# Antenna_Board_v4_1.net
KiCad netlist of a schematic drawn in EAGLE
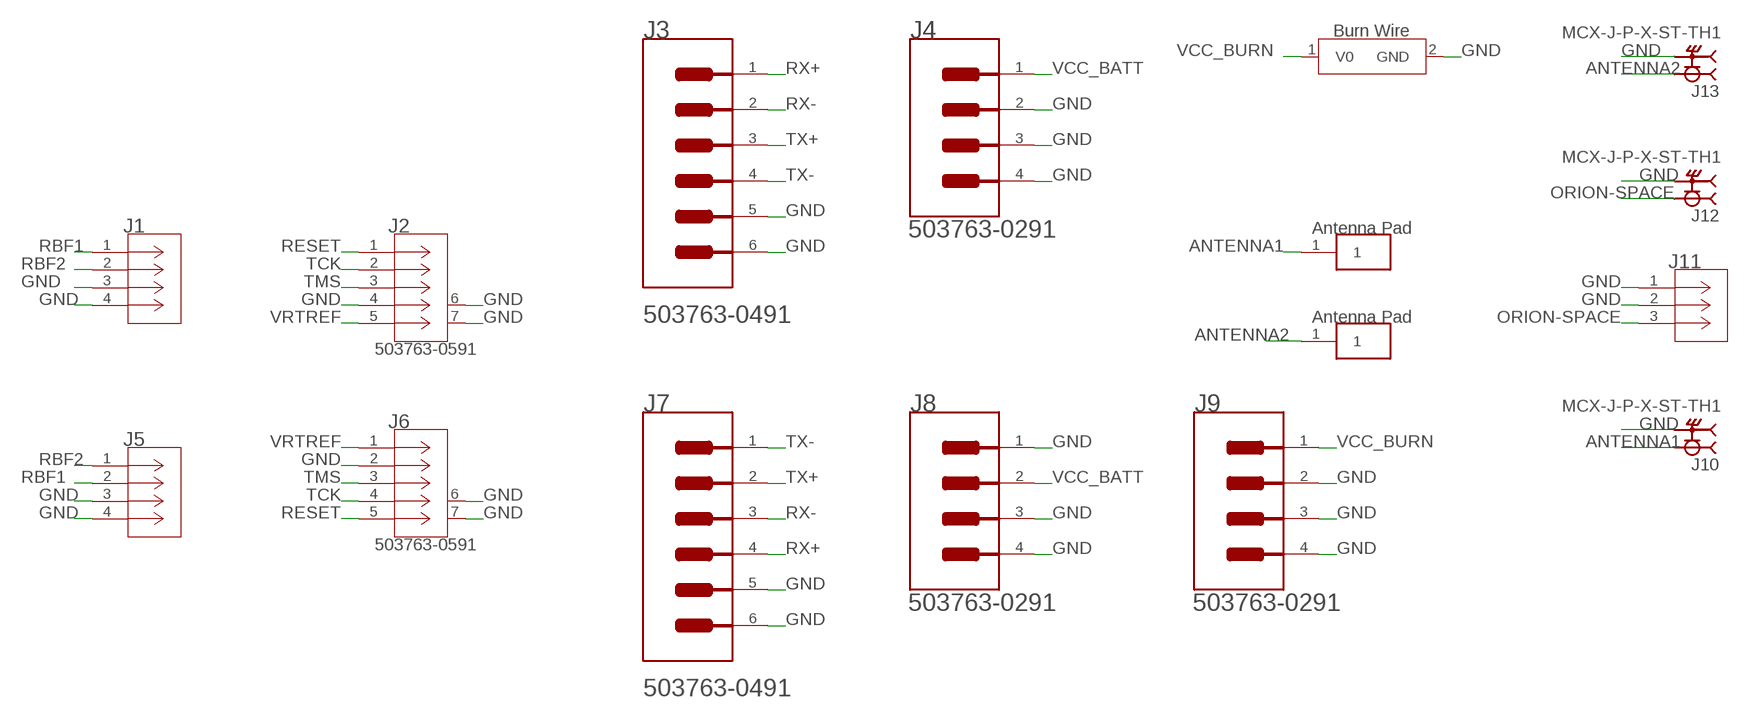
[diagram p0: schematic, sheet 1]

(export (version "E")
  (design (tool "Eeschema 10.0.6"))
  (components
    (comp (ref "J1")
      (value "5037630291")
      (footprint "eagle-import:CON_5037630291")
      (fields (field (name "COPYRIGHT") "Copyright (C) 2018 Accelerated Designs. All rights reserved"))
      (libsource (lib "eagle-import") (part "5037630291"))
    )
    (comp (ref "J2")
      (value "503763-0591")
      (footprint "eagle-import:CONN_5037630591_MOL")
      (fields (field (name "COPYRIGHT") "Copyright (C) 2018 Accelerated Designs. All rights reserved"))
      (libsource (lib "eagle-import") (part "503763-0591"))
    )
    (comp (ref "J3")
      (value "MOLEX_503763-0491MOLEX_503763-0491_0_0")
      (footprint "eagle-import:MOLEX_503763-0491_0")
      (fields
        (field (name "DIGIKEY_PART_NUMBER") "WM10655CT-ND")
        (field (name "MF") "Molex")
        (field (name "MOUSER_PART_NUMBER") "538-503763-0491")
      )
      (libsource (lib "eagle-import") (part "MOLEX_503763-0491MOLEX_503763-0491_0_0"))
    )
    (comp (ref "J4")
      (value "MOLEX_503763-0291MOLEX_503763-0291_0_0")
      (footprint "eagle-import:MOLEX_503763-0291_0")
      (fields
        (field (name "DIGIKEY_PART_NUMBER") "WM10654CT-ND")
        (field (name "MF") "Molex")
        (field (name "MOUSER_PART_NUMBER") "538-503763-0291")
      )
      (libsource (lib "eagle-import") (part "MOLEX_503763-0291MOLEX_503763-0291_0_0"))
    )
    (comp (ref "J5")
      (value "5037630291")
      (footprint "eagle-import:CON_5037630291")
      (fields (field (name "COPYRIGHT") "Copyright (C) 2018 Accelerated Designs. All rights reserved"))
      (libsource (lib "eagle-import") (part "5037630291"))
    )
    (comp (ref "J6")
      (value "503763-0591")
      (footprint "eagle-import:CONN_5037630591_MOL")
      (fields (field (name "COPYRIGHT") "Copyright (C) 2018 Accelerated Designs. All rights reserved"))
      (libsource (lib "eagle-import") (part "503763-0591"))
    )
    (comp (ref "J7")
      (value "MOLEX_503763-0491MOLEX_503763-0491_0_0")
      (footprint "eagle-import:MOLEX_503763-0491_0")
      (fields
        (field (name "DIGIKEY_PART_NUMBER") "WM10655CT-ND")
        (field (name "MF") "Molex")
        (field (name "MOUSER_PART_NUMBER") "538-503763-0491")
      )
      (libsource (lib "eagle-import") (part "MOLEX_503763-0491MOLEX_503763-0491_0_0"))
    )
    (comp (ref "J8")
      (value "MOLEX_503763-0291MOLEX_503763-0291_0_0")
      (footprint "eagle-import:MOLEX_503763-0291_0")
      (fields
        (field (name "DIGIKEY_PART_NUMBER") "WM10654CT-ND")
        (field (name "MF") "Molex")
        (field (name "MOUSER_PART_NUMBER") "538-503763-0291")
      )
      (libsource (lib "eagle-import") (part "MOLEX_503763-0291MOLEX_503763-0291_0_0"))
    )
    (comp (ref "J9")
      (value "MOLEX_503763-0291MOLEX_503763-0291_0_0")
      (footprint "eagle-import:MOLEX_503763-0291_0")
      (fields
        (field (name "DIGIKEY_PART_NUMBER") "WM10654CT-ND")
        (field (name "MF") "Molex")
        (field (name "MOUSER_PART_NUMBER") "538-503763-0291")
      )
      (libsource (lib "eagle-import") (part "MOLEX_503763-0291MOLEX_503763-0291_0_0"))
    )
    (comp (ref "J10")
      (value "MCX-J-P-X-ST-TH1")
      (footprint "eagle-import:SAMTEC_MCX-J-P-X-ST-TH1")
      (fields
        (field (name "DIGI-KEY_PART_NUMBER") "SAM8944-ND")
        (field (name "MF") "Samtec")
        (field (name "MP") "MCX-J-P-H-ST-TH1")
      )
      (libsource (lib "eagle-import") (part "MCX-J-P-X-ST-TH1"))
    )
    (comp (ref "J11")
      (value "U.FL-R-SMT-1(01)")
      (footprint "eagle-import:CONN_-SMT-1(01)")
      (fields (field (name "COPYRIGHT") "Copyright (C) 2018 Accelerated Designs. All rights reserved"))
      (libsource (lib "eagle-import") (part "U.FL-R-SMT-1(01)"))
    )
    (comp (ref "J12")
      (value "MCX-J-P-X-ST-TH1")
      (footprint "eagle-import:SAMTEC_MCX-J-P-X-ST-TH1")
      (fields
        (field (name "DIGI-KEY_PART_NUMBER") "SAM8944-ND")
        (field (name "MF") "Samtec")
        (field (name "MP") "MCX-J-P-H-ST-TH1")
      )
      (libsource (lib "eagle-import") (part "MCX-J-P-X-ST-TH1"))
    )
    (comp (ref "J13")
      (value "MCX-J-P-X-ST-TH1")
      (footprint "eagle-import:SAMTEC_MCX-J-P-X-ST-TH1")
      (fields
        (field (name "DIGI-KEY_PART_NUMBER") "SAM8944-ND")
        (field (name "MF") "Samtec")
        (field (name "MP") "MCX-J-P-H-ST-TH1")
      )
      (libsource (lib "eagle-import") (part "MCX-J-P-X-ST-TH1"))
    )
    (comp (ref "U$1")
      (value "ANTENNA_PAD+HOLES")
      (footprint "eagle-import:ANTENNA_PAD+HOLES")
      (libsource (lib "eagle-import") (part "ANTENNA_PAD+HOLES"))
    )
    (comp (ref "U$2")
      (value "ANTENNA_PAD+HOLES")
      (footprint "eagle-import:ANTENNA_PAD+HOLES")
      (libsource (lib "eagle-import") (part "ANTENNA_PAD+HOLES"))
    )
    (comp (ref "U$3")
      (value "BURNWIRE")
      (footprint "eagle-import:BURNWIRE")
      (libsource (lib "eagle-import") (part "BURNWIRE"))
    )
  )
  (nets
    (net (code "1") (name "/ANTENNA1") (class "Default")
      (node (ref "J10") (pin "1") (pinfunction "1_1") (pintype "passive"))
      (node (ref "U$1") (pin "1") (pinfunction "1_1") (pintype "bidirectional"))
    )
    (net (code "2") (name "/ANTENNA2") (class "Default")
      (node (ref "J13") (pin "1") (pinfunction "1_1") (pintype "passive"))
      (node (ref "U$2") (pin "1") (pinfunction "1_1") (pintype "bidirectional"))
    )
    (net (code "3") (name "/GND") (class "Default")
      (node (ref "J1") (pin "3") (pinfunction "3_3") (pintype "passive"))
      (node (ref "J1") (pin "4") (pinfunction "4_4") (pintype "passive"))
      (node (ref "J10") (pin "S1") (pinfunction "2_S1") (pintype "passive"))
      (node (ref "J10") (pin "S2") (pinfunction "2_S2") (pintype "passive"))
      (node (ref "J10") (pin "S3") (pinfunction "2_S3") (pintype "passive"))
      (node (ref "J10") (pin "S4") (pinfunction "2_S4") (pintype "passive"))
      (node (ref "J11") (pin "1") (pinfunction "1_1") (pintype "passive"))
      (node (ref "J11") (pin "2") (pinfunction "2_2") (pintype "passive"))
      (node (ref "J12") (pin "S1") (pinfunction "2_S1") (pintype "passive"))
      (node (ref "J12") (pin "S2") (pinfunction "2_S2") (pintype "passive"))
      (node (ref "J12") (pin "S3") (pinfunction "2_S3") (pintype "passive"))
      (node (ref "J12") (pin "S4") (pinfunction "2_S4") (pintype "passive"))
      (node (ref "J13") (pin "S1") (pinfunction "2_S1") (pintype "passive"))
      (node (ref "J13") (pin "S2") (pinfunction "2_S2") (pintype "passive"))
      (node (ref "J13") (pin "S3") (pinfunction "2_S3") (pintype "passive"))
      (node (ref "J13") (pin "S4") (pinfunction "2_S4") (pintype "passive"))
      (node (ref "J2") (pin "4") (pinfunction "4_4") (pintype "passive"))
      (node (ref "J2") (pin "6") (pinfunction "6_6") (pintype "bidirectional"))
      (node (ref "J2") (pin "7") (pinfunction "7_7") (pintype "bidirectional"))
      (node (ref "J3") (pin "5") (pinfunction "MNT_1_5") (pintype "passive"))
      (node (ref "J3") (pin "6") (pinfunction "MNT_2_6") (pintype "passive"))
      (node (ref "J4") (pin "2") (pinfunction "2_2") (pintype "bidirectional"))
      (node (ref "J4") (pin "3") (pinfunction "MNT_1_3") (pintype "bidirectional"))
      (node (ref "J4") (pin "4") (pinfunction "MNT_2_4") (pintype "bidirectional"))
      (node (ref "J5") (pin "3") (pinfunction "3_3") (pintype "passive"))
      (node (ref "J5") (pin "4") (pinfunction "4_4") (pintype "passive"))
      (node (ref "J6") (pin "2") (pinfunction "2_2") (pintype "passive"))
      (node (ref "J6") (pin "6") (pinfunction "6_6") (pintype "bidirectional"))
      (node (ref "J6") (pin "7") (pinfunction "7_7") (pintype "bidirectional"))
      (node (ref "J7") (pin "5") (pinfunction "MNT_1_5") (pintype "passive"))
      (node (ref "J7") (pin "6") (pinfunction "MNT_2_6") (pintype "passive"))
      (node (ref "J8") (pin "1") (pinfunction "1_1") (pintype "bidirectional"))
      (node (ref "J8") (pin "3") (pinfunction "MNT_1_3") (pintype "bidirectional"))
      (node (ref "J8") (pin "4") (pinfunction "MNT_2_4") (pintype "bidirectional"))
      (node (ref "J9") (pin "2") (pinfunction "2_2") (pintype "bidirectional"))
      (node (ref "J9") (pin "3") (pinfunction "MNT_1_3") (pintype "bidirectional"))
      (node (ref "J9") (pin "4") (pinfunction "MNT_2_4") (pintype "bidirectional"))
      (node (ref "U$3") (pin "2") (pinfunction "GND_2") (pintype "bidirectional"))
    )
    (net (code "4") (name "/ORION-SPACE") (class "Default")
      (node (ref "J11") (pin "3") (pinfunction "3_3") (pintype "passive"))
      (node (ref "J12") (pin "1") (pinfunction "1_1") (pintype "passive"))
    )
    (net (code "5") (name "/RBF1") (class "Default")
      (node (ref "J1") (pin "1") (pinfunction "1_1") (pintype "passive"))
      (node (ref "J5") (pin "2") (pinfunction "2_2") (pintype "passive"))
    )
    (net (code "6") (name "/RBF2") (class "Default")
      (node (ref "J1") (pin "2") (pinfunction "2_2") (pintype "passive"))
      (node (ref "J5") (pin "1") (pinfunction "1_1") (pintype "passive"))
    )
    (net (code "7") (name "/RESET") (class "Default")
      (node (ref "J2") (pin "1") (pinfunction "1_1") (pintype "passive"))
      (node (ref "J6") (pin "5") (pinfunction "5_5") (pintype "passive"))
    )
    (net (code "8") (name "/RX+") (class "Default")
      (node (ref "J3") (pin "1") (pinfunction "1_1") (pintype "passive"))
      (node (ref "J7") (pin "4") (pinfunction "4_4") (pintype "passive"))
    )
    (net (code "9") (name "/RX-") (class "Default")
      (node (ref "J3") (pin "2") (pinfunction "2_2") (pintype "passive"))
      (node (ref "J7") (pin "3") (pinfunction "3_3") (pintype "passive"))
    )
    (net (code "10") (name "/TCK") (class "Default")
      (node (ref "J2") (pin "2") (pinfunction "2_2") (pintype "passive"))
      (node (ref "J6") (pin "4") (pinfunction "4_4") (pintype "passive"))
    )
    (net (code "11") (name "/TMS") (class "Default")
      (node (ref "J2") (pin "3") (pinfunction "3_3") (pintype "passive"))
      (node (ref "J6") (pin "3") (pinfunction "3_3") (pintype "passive"))
    )
    (net (code "12") (name "/TX+") (class "Default")
      (node (ref "J3") (pin "3") (pinfunction "3_3") (pintype "passive"))
      (node (ref "J7") (pin "2") (pinfunction "2_2") (pintype "passive"))
    )
    (net (code "13") (name "/TX-") (class "Default")
      (node (ref "J3") (pin "4") (pinfunction "4_4") (pintype "passive"))
      (node (ref "J7") (pin "1") (pinfunction "1_1") (pintype "passive"))
    )
    (net (code "14") (name "/VCC_BATT") (class "Default")
      (node (ref "J4") (pin "1") (pinfunction "1_1") (pintype "bidirectional"))
      (node (ref "J8") (pin "2") (pinfunction "2_2") (pintype "bidirectional"))
    )
    (net (code "15") (name "/VCC_BURN") (class "Default")
      (node (ref "J9") (pin "1") (pinfunction "1_1") (pintype "bidirectional"))
      (node (ref "U$3") (pin "1") (pinfunction "V0_1") (pintype "bidirectional"))
    )
    (net (code "16") (name "/VRTREF") (class "Default")
      (node (ref "J2") (pin "5") (pinfunction "5_5") (pintype "passive"))
      (node (ref "J6") (pin "1") (pinfunction "1_1") (pintype "passive"))
    )
  )
)
